# HM_Nightfall-mini-2e_v1.net
KiCad netlist of a schematic drawn in EAGLE
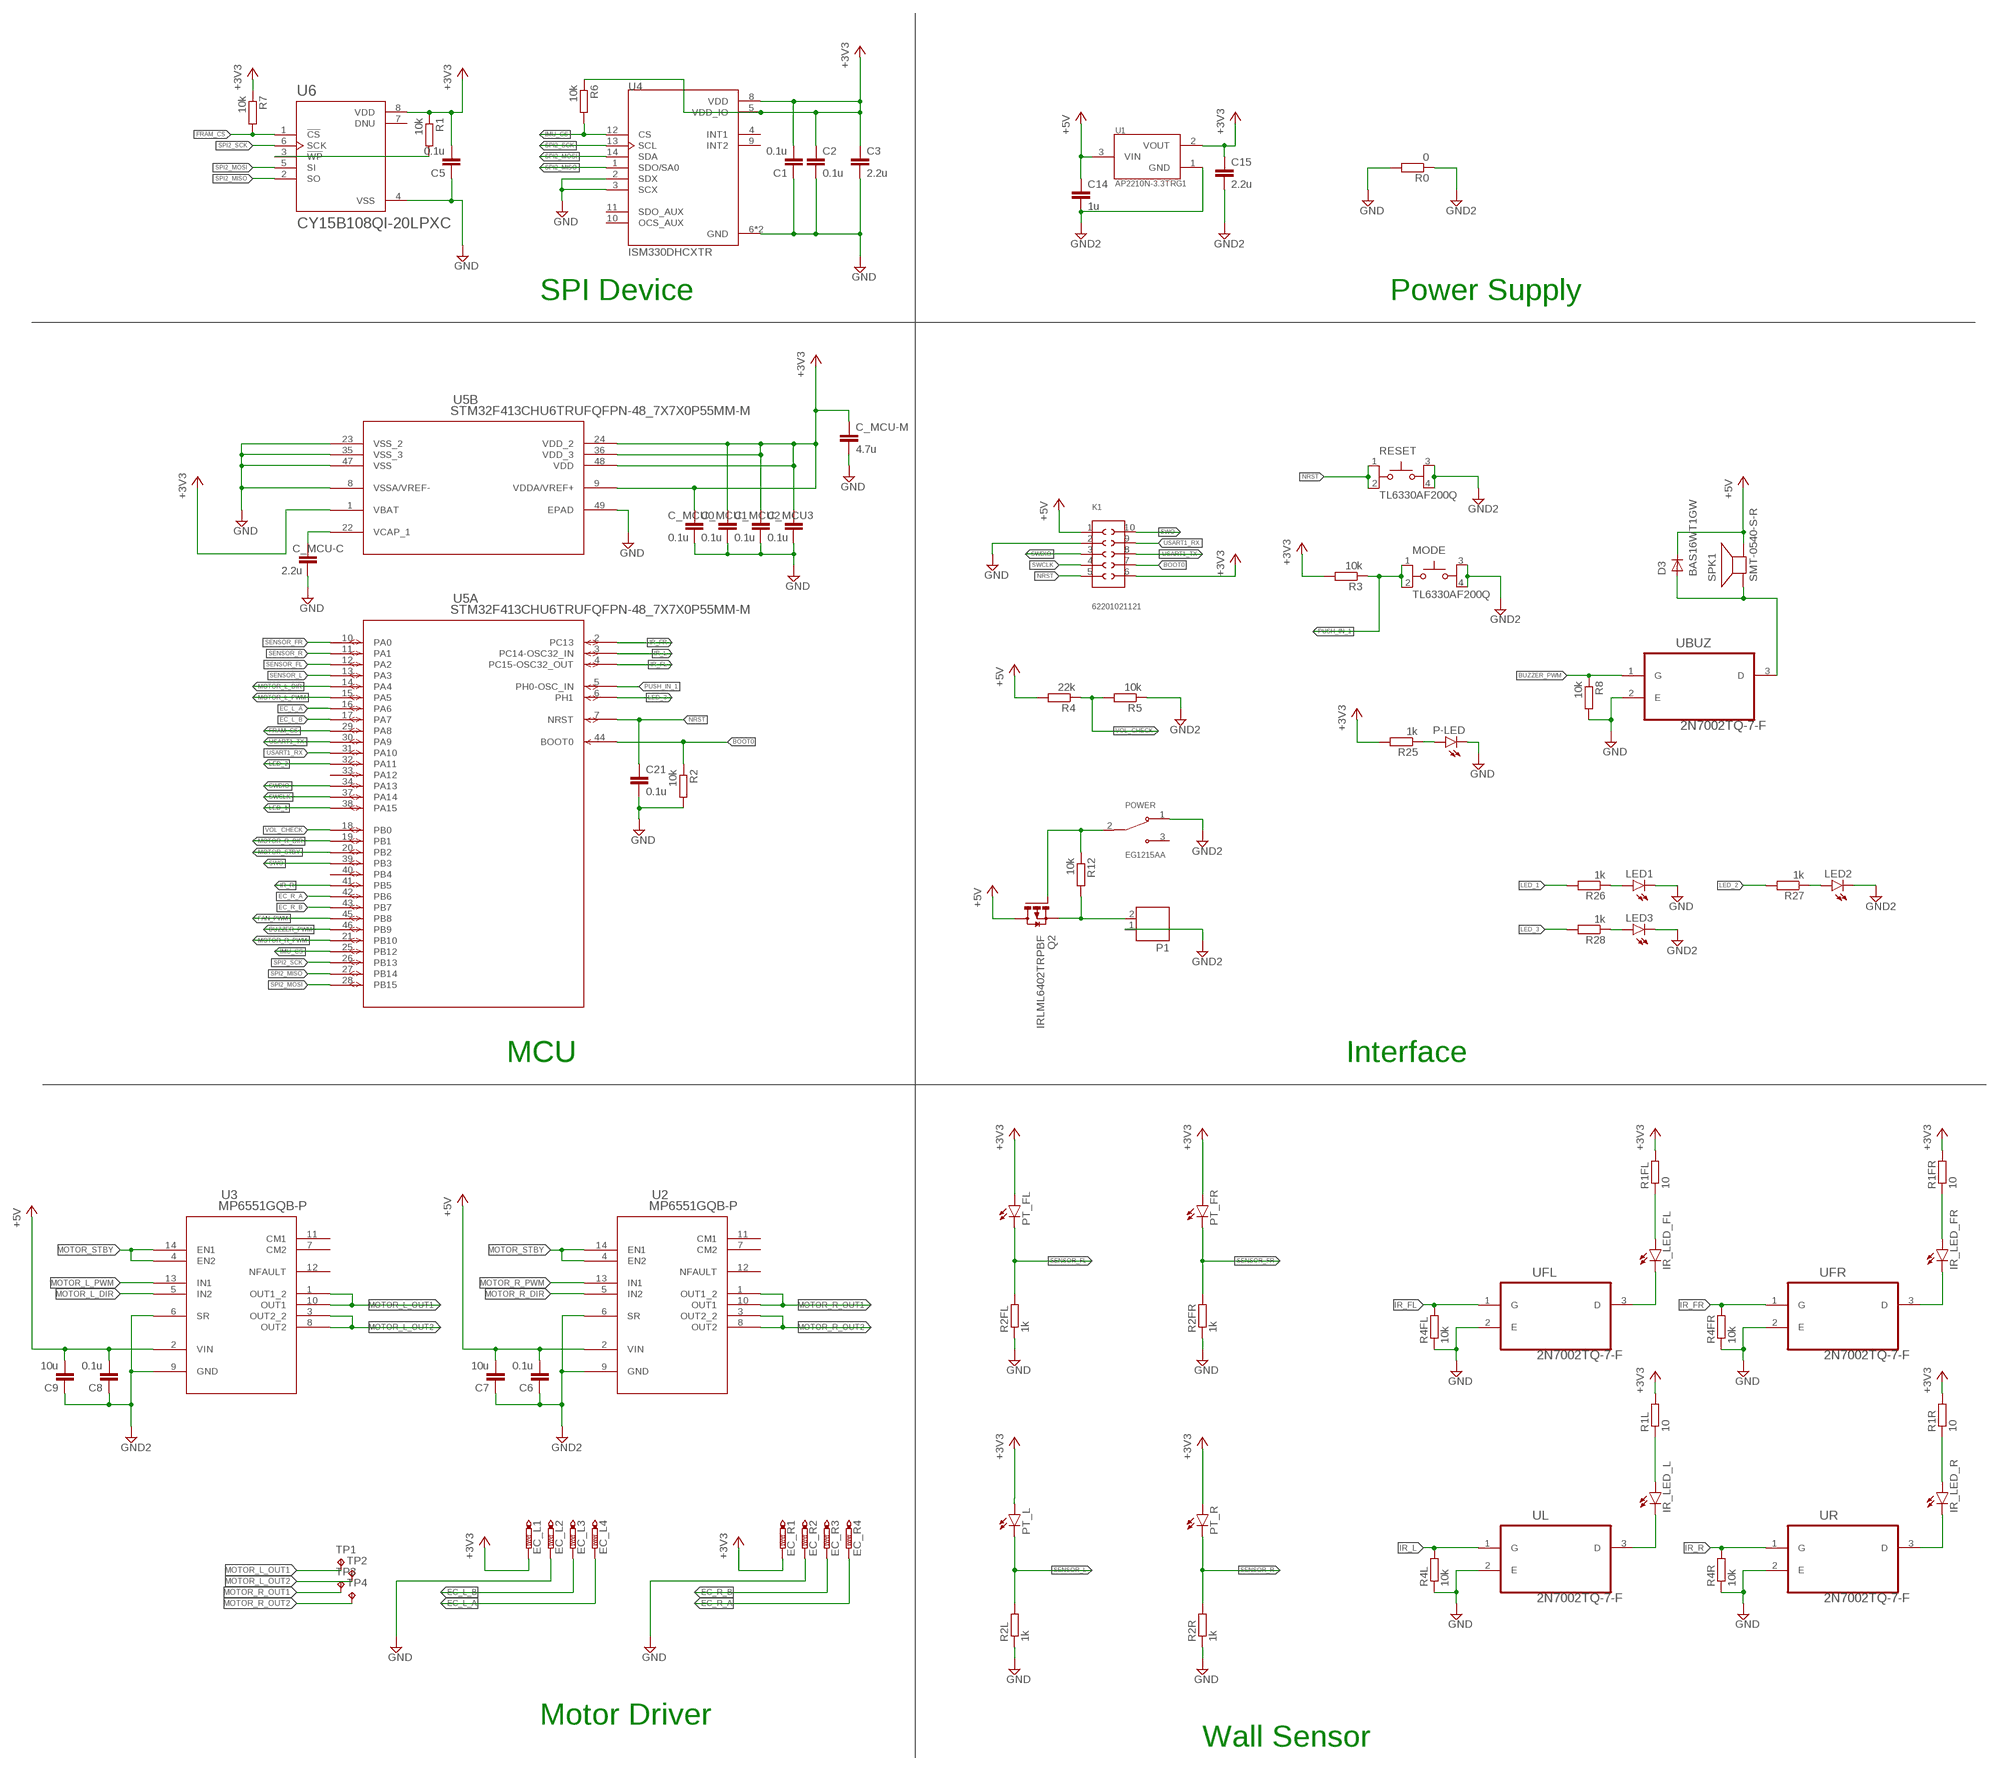
[diagram p0: schematic, sheet 1]

(export (version "E")
  (design (tool "Eeschema 10.0.6"))
  (components
    (comp (ref "C1")
      (value "0.1u")
      (footprint "eagle-import:C0402")
      (libsource (lib "eagle-import") (part "C-EUC0402"))
    )
    (comp (ref "C2")
      (value "0.1u")
      (footprint "eagle-import:C0402")
      (libsource (lib "eagle-import") (part "C-EUC0402"))
    )
    (comp (ref "C3")
      (value "2.2u")
      (footprint "eagle-import:C0402")
      (libsource (lib "eagle-import") (part "C-EUC0402"))
    )
    (comp (ref "C5")
      (value "0.1u")
      (footprint "eagle-import:C0402")
      (libsource (lib "eagle-import") (part "C-EUC0402"))
    )
    (comp (ref "C6")
      (value "0.1u")
      (footprint "eagle-import:C0402")
      (libsource (lib "eagle-import") (part "C-EUC0402"))
    )
    (comp (ref "C7")
      (value "10u")
      (footprint "eagle-import:C0402")
      (libsource (lib "eagle-import") (part "C-EUC0402"))
    )
    (comp (ref "C8")
      (value "0.1u")
      (footprint "eagle-import:C0402")
      (libsource (lib "eagle-import") (part "C-EUC0402"))
    )
    (comp (ref "C9")
      (value "10u")
      (footprint "eagle-import:C0402")
      (libsource (lib "eagle-import") (part "C-EUC0402"))
    )
    (comp (ref "C14")
      (value "1u")
      (footprint "eagle-import:C0402")
      (libsource (lib "eagle-import") (part "C-EUC0402"))
    )
    (comp (ref "C15")
      (value "2.2u")
      (footprint "eagle-import:C0402")
      (libsource (lib "eagle-import") (part "C-EUC0402"))
    )
    (comp (ref "C21")
      (value "0.1u")
      (footprint "eagle-import:C0402")
      (libsource (lib "eagle-import") (part "C-EUC0402"))
    )
    (comp (ref "C_MCU-C")
      (value "2.2u")
      (footprint "eagle-import:C0402")
      (libsource (lib "eagle-import") (part "C-EUC0402"))
    )
    (comp (ref "C_MCU-M")
      (value "4.7u")
      (footprint "eagle-import:C0402")
      (libsource (lib "eagle-import") (part "C-EUC0402"))
    )
    (comp (ref "C_MCU0")
      (value "0.1u")
      (footprint "eagle-import:C0402")
      (libsource (lib "eagle-import") (part "C-EUC0402"))
    )
    (comp (ref "C_MCU1")
      (value "0.1u")
      (footprint "eagle-import:C0402")
      (libsource (lib "eagle-import") (part "C-EUC0402"))
    )
    (comp (ref "C_MCU2")
      (value "0.1u")
      (footprint "eagle-import:C0402")
      (libsource (lib "eagle-import") (part "C-EUC0402"))
    )
    (comp (ref "C_MCU3")
      (value "0.1u")
      (footprint "eagle-import:C0402")
      (libsource (lib "eagle-import") (part "C-EUC0402"))
    )
    (comp (ref "D3")
      (value "BAS16WT1GW")
      (footprint "eagle-import:SOT323")
      (fields (field (name "MF") "ON Semiconductor") (field (name "MP") "BAS16WT1G"))
      (libsource (lib "eagle-import") (part "BAS16WT1GW"))
    )
    (comp (ref "EC_L1")
      (value "PTR1TP06SQ")
      (footprint "eagle-import:TP06SQ")
      (libsource (lib "eagle-import") (part "PTR1TP06SQ"))
    )
    (comp (ref "EC_L2")
      (value "PTR1TP06SQ")
      (footprint "eagle-import:TP06SQ")
      (libsource (lib "eagle-import") (part "PTR1TP06SQ"))
    )
    (comp (ref "EC_L3")
      (value "PTR1TP06SQ")
      (footprint "eagle-import:TP06SQ")
      (libsource (lib "eagle-import") (part "PTR1TP06SQ"))
    )
    (comp (ref "EC_L4")
      (value "PTR1TP06SQ")
      (footprint "eagle-import:TP06SQ")
      (libsource (lib "eagle-import") (part "PTR1TP06SQ"))
    )
    (comp (ref "EC_R1")
      (value "PTR1TP06SQ")
      (footprint "eagle-import:TP06SQ")
      (libsource (lib "eagle-import") (part "PTR1TP06SQ"))
    )
    (comp (ref "EC_R2")
      (value "PTR1TP06SQ")
      (footprint "eagle-import:TP06SQ")
      (libsource (lib "eagle-import") (part "PTR1TP06SQ"))
    )
    (comp (ref "EC_R3")
      (value "PTR1TP06SQ")
      (footprint "eagle-import:TP06SQ")
      (libsource (lib "eagle-import") (part "PTR1TP06SQ"))
    )
    (comp (ref "EC_R4")
      (value "PTR1TP06SQ")
      (footprint "eagle-import:TP06SQ")
      (libsource (lib "eagle-import") (part "PTR1TP06SQ"))
    )
    (comp (ref "IR_LED_FL")
      (value "LED3MM")
      (footprint "eagle-import:LED3MM")
      (libsource (lib "eagle-import") (part "LED3MM"))
    )
    (comp (ref "IR_LED_FR")
      (value "LED3MM")
      (footprint "eagle-import:LED3MM")
      (libsource (lib "eagle-import") (part "LED3MM"))
    )
    (comp (ref "IR_LED_L")
      (value "LED3MM")
      (footprint "eagle-import:LED3MM")
      (libsource (lib "eagle-import") (part "LED3MM"))
    )
    (comp (ref "IR_LED_R")
      (value "LED3MM")
      (footprint "eagle-import:LED3MM")
      (libsource (lib "eagle-import") (part "LED3MM"))
    )
    (comp (ref "K1")
      (value "62201021121")
      (footprint "eagle-import:62201021121")
      (libsource (lib "eagle-import") (part "62201021121"))
    )
    (comp (ref "LED1")
      (value "LEDCHIPLED_0603")
      (footprint "eagle-import:CHIPLED_0603")
      (libsource (lib "eagle-import") (part "LEDCHIPLED_0603"))
    )
    (comp (ref "LED2")
      (value "LEDCHIPLED_0603")
      (footprint "eagle-import:CHIPLED_0603")
      (libsource (lib "eagle-import") (part "LEDCHIPLED_0603"))
    )
    (comp (ref "LED3")
      (value "LEDCHIPLED_0603")
      (footprint "eagle-import:CHIPLED_0603")
      (libsource (lib "eagle-import") (part "LEDCHIPLED_0603"))
    )
    (comp (ref "MODE")
      (value "TL6330AF200Q")
      (footprint "eagle-import:SW_TL6330AF200Q")
      (fields (field (name "MF") "E-Switch"))
      (libsource (lib "eagle-import") (part "TL6330AF200Q"))
    )
    (comp (ref "P-LED")
      (value "LEDCHIPLED_0603")
      (footprint "eagle-import:CHIPLED_0603")
      (libsource (lib "eagle-import") (part "LEDCHIPLED_0603"))
    )
    (comp (ref "P1")
      (value "JST-PH2")
      (footprint "eagle-import:JST-PH2")
      (libsource (lib "eagle-import") (part "JST-PH2"))
    )
    (comp (ref "POWER")
      (value "EG1215AA")
      (footprint "eagle-import:SW_EG1215AA")
      (fields (field (name "MF") "E-Switch"))
      (libsource (lib "eagle-import") (part "EG1215AA"))
    )
    (comp (ref "PT_FL")
      (value "LED3MM")
      (footprint "eagle-import:LED3MM")
      (libsource (lib "eagle-import") (part "LED3MM"))
    )
    (comp (ref "PT_FR")
      (value "LED3MM")
      (footprint "eagle-import:LED3MM")
      (libsource (lib "eagle-import") (part "LED3MM"))
    )
    (comp (ref "PT_L")
      (value "LED3MM")
      (footprint "eagle-import:LED3MM")
      (libsource (lib "eagle-import") (part "LED3MM"))
    )
    (comp (ref "PT_R")
      (value "LED3MM")
      (footprint "eagle-import:LED3MM")
      (libsource (lib "eagle-import") (part "LED3MM"))
    )
    (comp (ref "Q2")
      (value "IRLML6402TRPBF")
      (footprint "eagle-import:SOT23")
      (fields (field (name "MF") "Infineon Technologies") (field (name "MP") "IRLML6402"))
      (libsource (lib "eagle-import") (part "IRLML6402TRPBF"))
    )
    (comp (ref "R0")
      (value "0")
      (footprint "eagle-import:R0402")
      (libsource (lib "eagle-import") (part "R-EU_R0402"))
    )
    (comp (ref "R1")
      (value "10k")
      (footprint "eagle-import:R0402")
      (libsource (lib "eagle-import") (part "R-EU_R0402"))
    )
    (comp (ref "R1FL")
      (value "10")
      (footprint "eagle-import:R0402")
      (libsource (lib "eagle-import") (part "R-EU_R0402"))
    )
    (comp (ref "R1FR")
      (value "10")
      (footprint "eagle-import:R0402")
      (libsource (lib "eagle-import") (part "R-EU_R0402"))
    )
    (comp (ref "R1L")
      (value "10")
      (footprint "eagle-import:R0402")
      (libsource (lib "eagle-import") (part "R-EU_R0402"))
    )
    (comp (ref "R1R")
      (value "10")
      (footprint "eagle-import:R0402")
      (libsource (lib "eagle-import") (part "R-EU_R0402"))
    )
    (comp (ref "R2")
      (value "10k")
      (footprint "eagle-import:R0402")
      (libsource (lib "eagle-import") (part "R-EU_R0402"))
    )
    (comp (ref "R2FL")
      (value "1k")
      (footprint "eagle-import:R0402")
      (libsource (lib "eagle-import") (part "R-EU_R0402"))
    )
    (comp (ref "R2FR")
      (value "1k")
      (footprint "eagle-import:R0402")
      (libsource (lib "eagle-import") (part "R-EU_R0402"))
    )
    (comp (ref "R2L")
      (value "1k")
      (footprint "eagle-import:R0402")
      (libsource (lib "eagle-import") (part "R-EU_R0402"))
    )
    (comp (ref "R2R")
      (value "1k")
      (footprint "eagle-import:R0402")
      (libsource (lib "eagle-import") (part "R-EU_R0402"))
    )
    (comp (ref "R3")
      (value "10k")
      (footprint "eagle-import:R0402")
      (libsource (lib "eagle-import") (part "R-EU_R0402"))
    )
    (comp (ref "R4")
      (value "22k")
      (footprint "eagle-import:R0402")
      (libsource (lib "eagle-import") (part "R-EU_R0402"))
    )
    (comp (ref "R4FL")
      (value "10k")
      (footprint "eagle-import:R0402")
      (libsource (lib "eagle-import") (part "R-EU_R0402"))
    )
    (comp (ref "R4FR")
      (value "10k")
      (footprint "eagle-import:R0402")
      (libsource (lib "eagle-import") (part "R-EU_R0402"))
    )
    (comp (ref "R4L")
      (value "10k")
      (footprint "eagle-import:R0402")
      (libsource (lib "eagle-import") (part "R-EU_R0402"))
    )
    (comp (ref "R4R")
      (value "10k")
      (footprint "eagle-import:R0402")
      (libsource (lib "eagle-import") (part "R-EU_R0402"))
    )
    (comp (ref "R5")
      (value "10k")
      (footprint "eagle-import:R0402")
      (libsource (lib "eagle-import") (part "R-EU_R0402"))
    )
    (comp (ref "R6")
      (value "10k")
      (footprint "eagle-import:R0402")
      (libsource (lib "eagle-import") (part "R-EU_R0402"))
    )
    (comp (ref "R7")
      (value "10k")
      (footprint "eagle-import:R0402")
      (libsource (lib "eagle-import") (part "R-EU_R0402"))
    )
    (comp (ref "R8")
      (value "10k")
      (footprint "eagle-import:R0402")
      (libsource (lib "eagle-import") (part "R-EU_R0402"))
    )
    (comp (ref "R12")
      (value "10k")
      (footprint "eagle-import:R0402")
      (libsource (lib "eagle-import") (part "R-EU_R0402"))
    )
    (comp (ref "R25")
      (value "1k")
      (footprint "eagle-import:R0402")
      (libsource (lib "eagle-import") (part "R-EU_R0402"))
    )
    (comp (ref "R26")
      (value "1k")
      (footprint "eagle-import:R0402")
      (libsource (lib "eagle-import") (part "R-EU_R0402"))
    )
    (comp (ref "R27")
      (value "1k")
      (footprint "eagle-import:R0402")
      (libsource (lib "eagle-import") (part "R-EU_R0402"))
    )
    (comp (ref "R28")
      (value "1k")
      (footprint "eagle-import:R0402")
      (libsource (lib "eagle-import") (part "R-EU_R0402"))
    )
    (comp (ref "RESET")
      (value "TL6330AF200Q")
      (footprint "eagle-import:SW_TL6330AF200Q")
      (fields (field (name "MF") "E-Switch"))
      (libsource (lib "eagle-import") (part "TL6330AF200Q"))
    )
    (comp (ref "SPK1")
      (value "SMT-0540-S-R")
      (footprint "eagle-import:SMT-0540-S-R")
      (fields (field (name "DIGI-KEY_PART_NUMBER") "668-1060-1-ND") (field (name "MF") "PUI"))
      (libsource (lib "eagle-import") (part "SMT-0540-S-R"))
    )
    (comp (ref "TP1")
      (value "TPB1,27")
      (footprint "eagle-import:B1,27")
      (libsource (lib "eagle-import") (part "TPB1,27"))
    )
    (comp (ref "TP2")
      (value "TPB1,27")
      (footprint "eagle-import:B1,27")
      (libsource (lib "eagle-import") (part "TPB1,27"))
    )
    (comp (ref "TP3")
      (value "TPB1,27")
      (footprint "eagle-import:B1,27")
      (libsource (lib "eagle-import") (part "TPB1,27"))
    )
    (comp (ref "TP4")
      (value "TPB1,27")
      (footprint "eagle-import:B1,27")
      (libsource (lib "eagle-import") (part "TPB1,27"))
    )
    (comp (ref "U1")
      (value "AP2210N-3.3TRG1")
      (footprint "eagle-import:SOT95P280X145-3N")
      (fields (field (name "MF") "Diodes Inc."))
      (libsource (lib "eagle-import") (part "AP2210N-3.3TRG1"))
    )
    (comp (ref "U2")
      (value "MP6551GQB-P")
      (footprint "eagle-import:QFN-14_MP6551_MNP")
      (fields (field (name "COPYRIGHT") "Copyright (C) 2025 Ultra Librarian. All rights reserved."))
      (libsource (lib "eagle-import") (part "MP6551GQB-P"))
    )
    (comp (ref "U3")
      (value "MP6551GQB-P")
      (footprint "eagle-import:QFN-14_MP6551_MNP")
      (fields (field (name "COPYRIGHT") "Copyright (C) 2025 Ultra Librarian. All rights reserved."))
      (libsource (lib "eagle-import") (part "MP6551GQB-P"))
    )
    (comp (ref "U4")
      (value "ISM330DHCXTR")
      (footprint "eagle-import:PQFN50P250X300X86-14N")
      (fields (field (name "MF") "STMicroelectronics"))
      (libsource (lib "eagle-import") (part "ISM330DHCXTR"))
    )
    (comp (ref "U5")
      (value "STM32F413CHU6TRUFQFPN-48_7X7X0P55MM-M")
      (footprint "eagle-import:UFQFPN-48_7X7X0P55MM-M")
      (fields
        (field (name "MANUFACTURER_PART_NUMBER") "STM32F413CHU6TR")
        (field (name "COPYRIGHT") "Copyright (C) 2026 Ultra Librarian. All rights reserved.")
      )
      (libsource (lib "eagle-import") (part "STM32F413CHU6TRUFQFPN-48_7X7X0P55MM-M"))
    )
    (comp (ref "U6")
      (value "CY15B108QI-20LPXC")
      (footprint "eagle-import:SON65P328X323X55-8N")
      (fields (field (name "MF") "Cypress Semiconductor"))
      (libsource (lib "eagle-import") (part "CY15B108QI-20LPXC"))
    )
    (comp (ref "UBUZ")
      (value "2N7002TQ-7-F")
      (footprint "eagle-import:SOT50P160X90-3N")
      (fields (field (name "MF") "Diodes Inc."))
      (libsource (lib "eagle-import") (part "2N7002TQ-7-F"))
    )
    (comp (ref "UFL")
      (value "2N7002TQ-7-F")
      (footprint "eagle-import:SOT50P160X90-3N")
      (fields (field (name "MF") "Diodes Inc."))
      (libsource (lib "eagle-import") (part "2N7002TQ-7-F"))
    )
    (comp (ref "UFR")
      (value "2N7002TQ-7-F")
      (footprint "eagle-import:SOT50P160X90-3N")
      (fields (field (name "MF") "Diodes Inc."))
      (libsource (lib "eagle-import") (part "2N7002TQ-7-F"))
    )
    (comp (ref "UL")
      (value "2N7002TQ-7-F")
      (footprint "eagle-import:SOT50P160X90-3N")
      (fields (field (name "MF") "Diodes Inc."))
      (libsource (lib "eagle-import") (part "2N7002TQ-7-F"))
    )
    (comp (ref "UR")
      (value "2N7002TQ-7-F")
      (footprint "eagle-import:SOT50P160X90-3N")
      (fields (field (name "MF") "Diodes Inc."))
      (libsource (lib "eagle-import") (part "2N7002TQ-7-F"))
    )
  )
  (nets
    (net (code "1") (name "+3V3") (class "Default")
      (node (ref "C1") (pin "2") (pinfunction "2_2") (pintype "passive"))
      (node (ref "C15") (pin "1") (pinfunction "1_1") (pintype "passive"))
      (node (ref "C2") (pin "1") (pinfunction "1_1") (pintype "passive"))
      (node (ref "C3") (pin "1") (pinfunction "1_1") (pintype "passive"))
      (node (ref "C5") (pin "2") (pinfunction "2_2") (pintype "passive"))
      (node (ref "C_MCU-M") (pin "1") (pinfunction "1_1") (pintype "passive"))
      (node (ref "C_MCU0") (pin "1") (pinfunction "1_1") (pintype "passive"))
      (node (ref "C_MCU1") (pin "1") (pinfunction "1_1") (pintype "passive"))
      (node (ref "C_MCU2") (pin "1") (pinfunction "1_1") (pintype "passive"))
      (node (ref "C_MCU3") (pin "1") (pinfunction "1_1") (pintype "passive"))
      (node (ref "EC_L1") (pin "TP") (pinfunction "TP_TP") (pintype "input"))
      (node (ref "EC_R1") (pin "TP") (pinfunction "TP_TP") (pintype "input"))
      (node (ref "K1") (pin "6") (pinfunction "6_6") (pintype "passive"))
      (node (ref "PT_FL") (pin "A") (pinfunction "A_A") (pintype "passive"))
      (node (ref "PT_FR") (pin "A") (pinfunction "A_A") (pintype "passive"))
      (node (ref "PT_L") (pin "A") (pinfunction "A_A") (pintype "passive"))
      (node (ref "PT_R") (pin "A") (pinfunction "A_A") (pintype "passive"))
      (node (ref "R1") (pin "1") (pinfunction "1_1") (pintype "passive"))
      (node (ref "R1FL") (pin "2") (pinfunction "2_2") (pintype "passive"))
      (node (ref "R1FR") (pin "2") (pinfunction "2_2") (pintype "passive"))
      (node (ref "R1L") (pin "2") (pinfunction "2_2") (pintype "passive"))
      (node (ref "R1R") (pin "2") (pinfunction "2_2") (pintype "passive"))
      (node (ref "R25") (pin "2") (pinfunction "2_2") (pintype "passive"))
      (node (ref "R3") (pin "2") (pinfunction "2_2") (pintype "passive"))
      (node (ref "R6") (pin "1") (pinfunction "1_1") (pintype "passive"))
      (node (ref "R7") (pin "1") (pinfunction "1_1") (pintype "passive"))
      (node (ref "U1") (pin "2") (pinfunction "VOUT_2") (pintype "output"))
      (node (ref "U4") (pin "5") (pinfunction "VDD_IO_5") (pintype "power_in"))
      (node (ref "U4") (pin "8") (pinfunction "VDD_8") (pintype "power_in"))
      (node (ref "U5") (pin "1") (pinfunction "VBAT_1") (pintype "power_in"))
      (node (ref "U5") (pin "24") (pinfunction "VDD_2_24") (pintype "power_in"))
      (node (ref "U5") (pin "36") (pinfunction "VDD_3_36") (pintype "power_in"))
      (node (ref "U5") (pin "48") (pinfunction "VDD_48") (pintype "power_in"))
      (node (ref "U5") (pin "9") (pinfunction "VDDA/VREF+_9") (pintype "power_in"))
      (node (ref "U6") (pin "8") (pinfunction "VDD_8") (pintype "power_in"))
    )
    (net (code "2") (name "+5V") (class "Default")
      (node (ref "C14") (pin "1") (pinfunction "1_1") (pintype "passive"))
      (node (ref "C6") (pin "2") (pinfunction "2_2") (pintype "passive"))
      (node (ref "C7") (pin "2") (pinfunction "2_2") (pintype "passive"))
      (node (ref "C8") (pin "2") (pinfunction "2_2") (pintype "passive"))
      (node (ref "C9") (pin "2") (pinfunction "2_2") (pintype "passive"))
      (node (ref "D3") (pin "3") (pinfunction "K_3") (pintype "passive"))
      (node (ref "K1") (pin "1") (pinfunction "1_1") (pintype "passive"))
      (node (ref "Q2") (pin "3") (pinfunction "D_3") (pintype "passive"))
      (node (ref "R4") (pin "2") (pinfunction "2_2") (pintype "passive"))
      (node (ref "SPK1") (pin "+") (pinfunction "-_+") (pintype "passive"))
      (node (ref "U1") (pin "3") (pinfunction "VIN_3") (pintype "input"))
      (node (ref "U2") (pin "2") (pinfunction "VIN_2") (pintype "power_in"))
      (node (ref "U3") (pin "2") (pinfunction "VIN_2") (pintype "power_in"))
    )
    (net (code "3") (name "BOOT0") (class "Default")
      (node (ref "K1") (pin "7") (pinfunction "7_7") (pintype "passive"))
      (node (ref "R2") (pin "1") (pinfunction "1_1") (pintype "passive"))
      (node (ref "U5") (pin "44") (pinfunction "BOOT0_44") (pintype "input"))
    )
    (net (code "4") (name "BUZZER_PWM") (class "Default")
      (node (ref "R8") (pin "1") (pinfunction "1_1") (pintype "passive"))
      (node (ref "U5") (pin "46") (pinfunction "PB9_46") (pintype "bidirectional"))
      (node (ref "UBUZ") (pin "1") (pinfunction "G_1") (pintype "passive"))
    )
    (net (code "5") (name "EC_L_A") (class "Default")
      (node (ref "EC_L4") (pin "TP") (pinfunction "TP_TP") (pintype "input"))
      (node (ref "U5") (pin "16") (pinfunction "PA6_16") (pintype "bidirectional"))
    )
    (net (code "6") (name "EC_L_B") (class "Default")
      (node (ref "EC_L3") (pin "TP") (pinfunction "TP_TP") (pintype "input"))
      (node (ref "U5") (pin "17") (pinfunction "PA7_17") (pintype "bidirectional"))
    )
    (net (code "7") (name "EC_R_A") (class "Default")
      (node (ref "EC_R4") (pin "TP") (pinfunction "TP_TP") (pintype "input"))
      (node (ref "U5") (pin "42") (pinfunction "PB6_42") (pintype "bidirectional"))
    )
    (net (code "8") (name "EC_R_B") (class "Default")
      (node (ref "EC_R3") (pin "TP") (pinfunction "TP_TP") (pintype "input"))
      (node (ref "U5") (pin "43") (pinfunction "PB7_43") (pintype "bidirectional"))
    )
    (net (code "9") (name "FAN_PWM") (class "Default")
      (node (ref "U5") (pin "45") (pinfunction "PB8_45") (pintype "bidirectional"))
    )
    (net (code "10") (name "FRAM_CS") (class "Default")
      (node (ref "R7") (pin "2") (pinfunction "2_2") (pintype "passive"))
      (node (ref "U5") (pin "29") (pinfunction "PA8_29") (pintype "bidirectional"))
      (node (ref "U6") (pin "1") (pinfunction "~{CS}_1") (pintype "input"))
    )
    (net (code "11") (name "GND") (class "Default")
      (node (ref "C1") (pin "1") (pinfunction "1_1") (pintype "passive"))
      (node (ref "C2") (pin "2") (pinfunction "2_2") (pintype "passive"))
      (node (ref "C21") (pin "2") (pinfunction "2_2") (pintype "passive"))
      (node (ref "C3") (pin "2") (pinfunction "2_2") (pintype "passive"))
      (node (ref "C5") (pin "1") (pinfunction "1_1") (pintype "passive"))
      (node (ref "C_MCU-C") (pin "2") (pinfunction "2_2") (pintype "passive"))
      (node (ref "C_MCU-M") (pin "2") (pinfunction "2_2") (pintype "passive"))
      (node (ref "C_MCU0") (pin "2") (pinfunction "2_2") (pintype "passive"))
      (node (ref "C_MCU1") (pin "2") (pinfunction "2_2") (pintype "passive"))
      (node (ref "C_MCU2") (pin "2") (pinfunction "2_2") (pintype "passive"))
      (node (ref "C_MCU3") (pin "2") (pinfunction "2_2") (pintype "passive"))
      (node (ref "EC_L2") (pin "TP") (pinfunction "TP_TP") (pintype "input"))
      (node (ref "EC_R2") (pin "TP") (pinfunction "TP_TP") (pintype "input"))
      (node (ref "K1") (pin "2") (pinfunction "2_2") (pintype "passive"))
      (node (ref "LED1") (pin "C") (pinfunction "C_C") (pintype "passive"))
      (node (ref "P-LED") (pin "C") (pinfunction "C_C") (pintype "passive"))
      (node (ref "R0") (pin "2") (pinfunction "2_2") (pintype "passive"))
      (node (ref "R2") (pin "2") (pinfunction "2_2") (pintype "passive"))
      (node (ref "R2FL") (pin "1") (pinfunction "1_1") (pintype "passive"))
      (node (ref "R2FR") (pin "1") (pinfunction "1_1") (pintype "passive"))
      (node (ref "R2L") (pin "1") (pinfunction "1_1") (pintype "passive"))
      (node (ref "R2R") (pin "1") (pinfunction "1_1") (pintype "passive"))
      (node (ref "R4FL") (pin "1") (pinfunction "1_1") (pintype "passive"))
      (node (ref "R4FR") (pin "1") (pinfunction "1_1") (pintype "passive"))
      (node (ref "R4L") (pin "1") (pinfunction "1_1") (pintype "passive"))
      (node (ref "R4R") (pin "1") (pinfunction "1_1") (pintype "passive"))
      (node (ref "R8") (pin "2") (pinfunction "2_2") (pintype "passive"))
      (node (ref "U4") (pin "2") (pinfunction "SDX_2") (pintype "bidirectional"))
      (node (ref "U4") (pin "3") (pinfunction "SCX_3") (pintype "bidirectional"))
      (node (ref "U4") (pin "6") (pinfunction "GND_6") (pintype "power_in"))
      (node (ref "U4") (pin "7") (pinfunction "GND_7") (pintype "power_in"))
      (node (ref "U5") (pin "23") (pinfunction "VSS_2_23") (pintype "power_in"))
      (node (ref "U5") (pin "35") (pinfunction "VSS_3_35") (pintype "power_in"))
      (node (ref "U5") (pin "47") (pinfunction "VSS_47") (pintype "power_in"))
      (node (ref "U5") (pin "49") (pinfunction "EPAD_49") (pintype "passive"))
      (node (ref "U5") (pin "8") (pinfunction "VSSA/VREF-_8") (pintype "power_in"))
      (node (ref "U6") (pin "4") (pinfunction "VSS_4") (pintype "power_in"))
      (node (ref "UBUZ") (pin "2") (pinfunction "E_2") (pintype "passive"))
      (node (ref "UFL") (pin "2") (pinfunction "E_2") (pintype "passive"))
      (node (ref "UFR") (pin "2") (pinfunction "E_2") (pintype "passive"))
      (node (ref "UL") (pin "2") (pinfunction "E_2") (pintype "passive"))
      (node (ref "UR") (pin "2") (pinfunction "E_2") (pintype "passive"))
    )
    (net (code "12") (name "GND2") (class "Default")
      (node (ref "C14") (pin "2") (pinfunction "2_2") (pintype "passive"))
      (node (ref "C15") (pin "2") (pinfunction "2_2") (pintype "passive"))
      (node (ref "C6") (pin "1") (pinfunction "1_1") (pintype "passive"))
      (node (ref "C7") (pin "1") (pinfunction "1_1") (pintype "passive"))
      (node (ref "C8") (pin "1") (pinfunction "1_1") (pintype "passive"))
      (node (ref "C9") (pin "1") (pinfunction "1_1") (pintype "passive"))
      (node (ref "LED2") (pin "C") (pinfunction "C_C") (pintype "passive"))
      (node (ref "LED3") (pin "C") (pinfunction "C_C") (pintype "passive"))
      (node (ref "MODE") (pin "3") (pinfunction "3_3") (pintype "passive"))
      (node (ref "MODE") (pin "4") (pinfunction "4_4") (pintype "passive"))
      (node (ref "P1") (pin "1") (pinfunction "1_1") (pintype "passive"))
      (node (ref "POWER") (pin "1") (pinfunction "1_1") (pintype "passive"))
      (node (ref "R0") (pin "1") (pinfunction "1_1") (pintype "passive"))
      (node (ref "R5") (pin "1") (pinfunction "1_1") (pintype "passive"))
      (node (ref "RESET") (pin "3") (pinfunction "3_3") (pintype "passive"))
      (node (ref "RESET") (pin "4") (pinfunction "4_4") (pintype "passive"))
      (node (ref "U1") (pin "1") (pinfunction "GND_1") (pintype "power_in"))
      (node (ref "U2") (pin "6") (pinfunction "SR_6") (pintype "passive"))
      (node (ref "U2") (pin "9") (pinfunction "GND_9") (pintype "power_in"))
      (node (ref "U3") (pin "6") (pinfunction "SR_6") (pintype "passive"))
      (node (ref "U3") (pin "9") (pinfunction "GND_9") (pintype "power_in"))
    )
    (net (code "13") (name "IMU_CS") (class "Default")
      (node (ref "R6") (pin "2") (pinfunction "2_2") (pintype "passive"))
      (node (ref "U4") (pin "12") (pinfunction "CS_12") (pintype "input"))
      (node (ref "U5") (pin "25") (pinfunction "PB12_25") (pintype "bidirectional"))
    )
    (net (code "14") (name "IR_FL") (class "Default")
      (node (ref "R4FL") (pin "2") (pinfunction "2_2") (pintype "passive"))
      (node (ref "U5") (pin "4") (pinfunction "PC15-OSC32_OUT_4") (pintype "bidirectional"))
      (node (ref "UFL") (pin "1") (pinfunction "G_1") (pintype "passive"))
    )
    (net (code "15") (name "IR_FR") (class "Default")
      (node (ref "R4FR") (pin "2") (pinfunction "2_2") (pintype "passive"))
      (node (ref "U5") (pin "2") (pinfunction "PC13_2") (pintype "bidirectional"))
      (node (ref "UFR") (pin "1") (pinfunction "G_1") (pintype "passive"))
    )
    (net (code "16") (name "IR_L") (class "Default")
      (node (ref "R4L") (pin "2") (pinfunction "2_2") (pintype "passive"))
      (node (ref "U5") (pin "3") (pinfunction "PC14-OSC32_IN_3") (pintype "bidirectional"))
      (node (ref "UL") (pin "1") (pinfunction "G_1") (pintype "passive"))
    )
    (net (code "17") (name "IR_R") (class "Default")
      (node (ref "R4R") (pin "2") (pinfunction "2_2") (pintype "passive"))
      (node (ref "U5") (pin "41") (pinfunction "PB5_41") (pintype "bidirectional"))
      (node (ref "UR") (pin "1") (pinfunction "G_1") (pintype "passive"))
    )
    (net (code "18") (name "LED_1") (class "Default")
      (node (ref "R26") (pin "2") (pinfunction "2_2") (pintype "passive"))
      (node (ref "U5") (pin "38") (pinfunction "PA15_38") (pintype "bidirectional"))
    )
    (net (code "19") (name "LED_2") (class "Default")
      (node (ref "R27") (pin "2") (pinfunction "2_2") (pintype "passive"))
      (node (ref "U5") (pin "32") (pinfunction "PA11_32") (pintype "bidirectional"))
    )
    (net (code "20") (name "LED_3") (class "Default")
      (node (ref "R28") (pin "2") (pinfunction "2_2") (pintype "passive"))
      (node (ref "U5") (pin "6") (pinfunction "PH1_6") (pintype "bidirectional"))
    )
    (net (code "21") (name "MOTOR_L_DIR") (class "Default")
      (node (ref "U3") (pin "5") (pinfunction "IN2_5") (pintype "input"))
      (node (ref "U5") (pin "14") (pinfunction "PA4_14") (pintype "bidirectional"))
    )
    (net (code "22") (name "MOTOR_L_OUT1") (class "Default")
      (node (ref "TP1") (pin "TP") (pinfunction "TP_TP") (pintype "input"))
      (node (ref "U3") (pin "1") (pinfunction "OUT1_2_1") (pintype "output"))
      (node (ref "U3") (pin "10") (pinfunction "OUT1_10") (pintype "output"))
    )
    (net (code "23") (name "MOTOR_L_OUT2") (class "Default")
      (node (ref "TP2") (pin "TP") (pinfunction "TP_TP") (pintype "input"))
      (node (ref "U3") (pin "3") (pinfunction "OUT2_2_3") (pintype "output"))
      (node (ref "U3") (pin "8") (pinfunction "OUT2_8") (pintype "output"))
    )
    (net (code "24") (name "MOTOR_L_PWM") (class "Default")
      (node (ref "U3") (pin "13") (pinfunction "IN1_13") (pintype "input"))
      (node (ref "U5") (pin "15") (pinfunction "PA5_15") (pintype "bidirectional"))
    )
    (net (code "25") (name "MOTOR_R_DIR") (class "Default")
      (node (ref "U2") (pin "5") (pinfunction "IN2_5") (pintype "input"))
      (node (ref "U5") (pin "19") (pinfunction "PB1_19") (pintype "bidirectional"))
    )
    (net (code "26") (name "MOTOR_R_OUT1") (class "Default")
      (node (ref "TP3") (pin "TP") (pinfunction "TP_TP") (pintype "input"))
      (node (ref "U2") (pin "1") (pinfunction "OUT1_2_1") (pintype "output"))
      (node (ref "U2") (pin "10") (pinfunction "OUT1_10") (pintype "output"))
    )
    (net (code "27") (name "MOTOR_R_OUT2") (class "Default")
      (node (ref "TP4") (pin "TP") (pinfunction "TP_TP") (pintype "input"))
      (node (ref "U2") (pin "3") (pinfunction "OUT2_2_3") (pintype "output"))
      (node (ref "U2") (pin "8") (pinfunction "OUT2_8") (pintype "output"))
    )
    (net (code "28") (name "MOTOR_R_PWM") (class "Default")
      (node (ref "U2") (pin "13") (pinfunction "IN1_13") (pintype "input"))
      (node (ref "U5") (pin "21") (pinfunction "PB10_21") (pintype "bidirectional"))
    )
    (net (code "29") (name "MOTOR_STBY") (class "Default")
      (node (ref "U2") (pin "14") (pinfunction "EN1_14") (pintype "input"))
      (node (ref "U2") (pin "4") (pinfunction "EN2_4") (pintype "input"))
      (node (ref "U3") (pin "14") (pinfunction "EN1_14") (pintype "input"))
      (node (ref "U3") (pin "4") (pinfunction "EN2_4") (pintype "input"))
      (node (ref "U5") (pin "20") (pinfunction "PB2_20") (pintype "bidirectional"))
    )
    (net (code "30") (name "NRST") (class "Default")
      (node (ref "C21") (pin "1") (pinfunction "1_1") (pintype "passive"))
      (node (ref "K1") (pin "5") (pinfunction "5_5") (pintype "passive"))
      (node (ref "RESET") (pin "1") (pinfunction "1_1") (pintype "passive"))
      (node (ref "RESET") (pin "2") (pinfunction "2_2") (pintype "passive"))
      (node (ref "U5") (pin "7") (pinfunction "NRST_7") (pintype "bidirectional"))
    )
    (net (code "31") (name "Net-(D3-A)") (class "Default")
      (node (ref "D3") (pin "1") (pinfunction "A_1") (pintype "passive"))
      (node (ref "SPK1") (pin "-") (pinfunction "+_-") (pintype "passive"))
      (node (ref "UBUZ") (pin "3") (pinfunction "D_3") (pintype "passive"))
    )
    (net (code "32") (name "Net-(IR_LED_FL-C)") (class "Default")
      (node (ref "IR_LED_FL") (pin "K") (pinfunction "C_K") (pintype "passive"))
      (node (ref "UFL") (pin "3") (pinfunction "D_3") (pintype "passive"))
    )
    (net (code "33") (name "Net-(IR_LED_FL-PadA)") (class "Default")
      (node (ref "IR_LED_FL") (pin "A") (pinfunction "A_A") (pintype "passive"))
      (node (ref "R1FL") (pin "1") (pinfunction "1_1") (pintype "passive"))
    )
    (net (code "34") (name "Net-(IR_LED_FR-C)") (class "Default")
      (node (ref "IR_LED_FR") (pin "K") (pinfunction "C_K") (pintype "passive"))
      (node (ref "UFR") (pin "3") (pinfunction "D_3") (pintype "passive"))
    )
    (net (code "35") (name "Net-(IR_LED_FR-PadA)") (class "Default")
      (node (ref "IR_LED_FR") (pin "A") (pinfunction "A_A") (pintype "passive"))
      (node (ref "R1FR") (pin "1") (pinfunction "1_1") (pintype "passive"))
    )
    (net (code "36") (name "Net-(IR_LED_L-C)") (class "Default")
      (node (ref "IR_LED_L") (pin "K") (pinfunction "C_K") (pintype "passive"))
      (node (ref "UL") (pin "3") (pinfunction "D_3") (pintype "passive"))
    )
    (net (code "37") (name "Net-(IR_LED_L-PadA)") (class "Default")
      (node (ref "IR_LED_L") (pin "A") (pinfunction "A_A") (pintype "passive"))
      (node (ref "R1L") (pin "1") (pinfunction "1_1") (pintype "passive"))
    )
    (net (code "38") (name "Net-(IR_LED_R-C)") (class "Default")
      (node (ref "IR_LED_R") (pin "K") (pinfunction "C_K") (pintype "passive"))
      (node (ref "UR") (pin "3") (pinfunction "D_3") (pintype "passive"))
    )
    (net (code "39") (name "Net-(IR_LED_R-PadA)") (class "Default")
      (node (ref "IR_LED_R") (pin "A") (pinfunction "A_A") (pintype "passive"))
      (node (ref "R1R") (pin "1") (pinfunction "1_1") (pintype "passive"))
    )
    (net (code "40") (name "Net-(LED1-PadA)") (class "Default")
      (node (ref "LED1") (pin "A") (pinfunction "A_A") (pintype "passive"))
      (node (ref "R26") (pin "1") (pinfunction "1_1") (pintype "passive"))
    )
    (net (code "41") (name "Net-(LED2-PadA)") (class "Default")
      (node (ref "LED2") (pin "A") (pinfunction "A_A") (pintype "passive"))
      (node (ref "R27") (pin "1") (pinfunction "1_1") (pintype "passive"))
    )
    (net (code "42") (name "Net-(LED3-PadA)") (class "Default")
      (node (ref "LED3") (pin "A") (pinfunction "A_A") (pintype "passive"))
      (node (ref "R28") (pin "1") (pinfunction "1_1") (pintype "passive"))
    )
    (net (code "43") (name "Net-(P-LED-PadA)") (class "Default")
      (node (ref "P-LED") (pin "A") (pinfunction "A_A") (pintype "passive"))
      (node (ref "R25") (pin "1") (pinfunction "1_1") (pintype "passive"))
    )
    (net (code "44") (name "Net-(Q2-G)") (class "Default")
      (node (ref "POWER") (pin "2") (pinfunction "2_2") (pintype "passive"))
      (node (ref "Q2") (pin "1") (pinfunction "G_1") (pintype "passive"))
      (node (ref "R12") (pin "1") (pinfunction "1_1") (pintype "passive"))
    )
    (net (code "45") (name "Net-(Q2-S)") (class "Default")
      (node (ref "P1") (pin "2") (pinfunction "2_2") (pintype "passive"))
      (node (ref "Q2") (pin "2") (pinfunction "S_2") (pintype "passive"))
      (node (ref "R12") (pin "2") (pinfunction "2_2") (pintype "passive"))
    )
    (net (code "46") (name "Net-(U5B-VCAP_1)") (class "Default")
      (node (ref "C_MCU-C") (pin "1") (pinfunction "1_1") (pintype "passive"))
      (node (ref "U5") (pin "22") (pinfunction "VCAP_1_22") (pintype "power_in"))
    )
    (net (code "47") (name "Net-(U6-~{WP})") (class "Default")
      (node (ref "R1") (pin "2") (pinfunction "2_2") (pintype "passive"))
      (node (ref "U6") (pin "3") (pinfunction "~{WP}_3") (pintype "input"))
    )
    (net (code "48") (name "PUSH_IN_1") (class "Default")
      (node (ref "MODE") (pin "1") (pinfunction "1_1") (pintype "passive"))
      (node (ref "MODE") (pin "2") (pinfunction "2_2") (pintype "passive"))
      (node (ref "R3") (pin "1") (pinfunction "1_1") (pintype "passive"))
      (node (ref "U5") (pin "5") (pinfunction "PH0-OSC_IN_5") (pintype "bidirectional"))
    )
    (net (code "49") (name "SENSOR_FL") (class "Default")
      (node (ref "PT_FL") (pin "K") (pinfunction "C_K") (pintype "passive"))
      (node (ref "R2FL") (pin "2") (pinfunction "2_2") (pintype "passive"))
      (node (ref "U5") (pin "12") (pinfunction "PA2_12") (pintype "bidirectional"))
    )
    (net (code "50") (name "SENSOR_FR") (class "Default")
      (node (ref "PT_FR") (pin "K") (pinfunction "C_K") (pintype "passive"))
      (node (ref "R2FR") (pin "2") (pinfunction "2_2") (pintype "passive"))
      (node (ref "U5") (pin "10") (pinfunction "PA0_10") (pintype "bidirectional"))
    )
    (net (code "51") (name "SENSOR_L") (class "Default")
      (node (ref "PT_L") (pin "K") (pinfunction "C_K") (pintype "passive"))
      (node (ref "R2L") (pin "2") (pinfunction "2_2") (pintype "passive"))
      (node (ref "U5") (pin "13") (pinfunction "PA3_13") (pintype "bidirectional"))
    )
    (net (code "52") (name "SENSOR_R") (class "Default")
      (node (ref "PT_R") (pin "K") (pinfunction "C_K") (pintype "passive"))
      (node (ref "R2R") (pin "2") (pinfunction "2_2") (pintype "passive"))
      (node (ref "U5") (pin "11") (pinfunction "PA1_11") (pintype "bidirectional"))
    )
    (net (code "53") (name "SPI2_MISO") (class "Default")
      (node (ref "U4") (pin "1") (pinfunction "SDO/SA0_1") (pintype "bidirectional"))
      (node (ref "U5") (pin "27") (pinfunction "PB14_27") (pintype "bidirectional"))
      (node (ref "U6") (pin "2") (pinfunction "SO_2") (pintype "output"))
    )
    (net (code "54") (name "SPI2_MOSI") (class "Default")
      (node (ref "U4") (pin "14") (pinfunction "SDA_14") (pintype "bidirectional"))
      (node (ref "U5") (pin "28") (pinfunction "PB15_28") (pintype "bidirectional"))
      (node (ref "U6") (pin "5") (pinfunction "SI_5") (pintype "input"))
    )
    (net (code "55") (name "SPI2_SCK") (class "Default")
      (node (ref "U4") (pin "13") (pinfunction "SCL_13") (pintype "input"))
      (node (ref "U5") (pin "26") (pinfunction "PB13_26") (pintype "bidirectional"))
      (node (ref "U6") (pin "6") (pinfunction "SCK_6") (pintype "input"))
    )
    (net (code "56") (name "SWCLK") (class "Default")
      (node (ref "K1") (pin "4") (pinfunction "4_4") (pintype "passive"))
      (node (ref "U5") (pin "37") (pinfunction "PA14_37") (pintype "bidirectional"))
    )
    (net (code "57") (name "SWDIO") (class "Default")
      (node (ref "K1") (pin "3") (pinfunction "3_3") (pintype "passive"))
      (node (ref "U5") (pin "34") (pinfunction "PA13_34") (pintype "bidirectional"))
    )
    (net (code "58") (name "SWO") (class "Default")
      (node (ref "K1") (pin "10") (pinfunction "10_10") (pintype "passive"))
      (node (ref "U5") (pin "39") (pinfunction "PB3_39") (pintype "bidirectional"))
    )
    (net (code "59") (name "USART1_RX") (class "Default")
      (node (ref "K1") (pin "9") (pinfunction "9_9") (pintype "passive"))
      (node (ref "U5") (pin "31") (pinfunction "PA10_31") (pintype "bidirectional"))
    )
    (net (code "60") (name "USART1_TX") (class "Default")
      (node (ref "K1") (pin "8") (pinfunction "8_8") (pintype "passive"))
      (node (ref "U5") (pin "30") (pinfunction "PA9_30") (pintype "bidirectional"))
    )
    (net (code "61") (name "VOL_CHECK") (class "Default")
      (node (ref "R4") (pin "1") (pinfunction "1_1") (pintype "passive"))
      (node (ref "R5") (pin "2") (pinfunction "2_2") (pintype "passive"))
      (node (ref "U5") (pin "18") (pinfunction "PB0_18") (pintype "bidirectional"))
    )
    (net (code "62") (name "unconnected-(POWER-Pad3)") (class "Default")
      (node (ref "POWER") (pin "3") (pinfunction "3_3") (pintype "passive"))
    )
    (net (code "63") (name "unconnected-(U2-CM1-Pad11)") (class "Default")
      (node (ref "U2") (pin "11") (pinfunction "CM1_11") (pintype "output"))
    )
    (net (code "64") (name "unconnected-(U2-CM2-Pad7)") (class "Default")
      (node (ref "U2") (pin "7") (pinfunction "CM2_7") (pintype "output"))
    )
    (net (code "65") (name "unconnected-(U2-NFAULT-Pad12)") (class "Default")
      (node (ref "U2") (pin "12") (pinfunction "NFAULT_12") (pintype "output"))
    )
    (net (code "66") (name "unconnected-(U3-CM1-Pad11)") (class "Default")
      (node (ref "U3") (pin "11") (pinfunction "CM1_11") (pintype "output"))
    )
    (net (code "67") (name "unconnected-(U3-CM2-Pad7)") (class "Default")
      (node (ref "U3") (pin "7") (pinfunction "CM2_7") (pintype "output"))
    )
    (net (code "68") (name "unconnected-(U3-NFAULT-Pad12)") (class "Default")
      (node (ref "U3") (pin "12") (pinfunction "NFAULT_12") (pintype "output"))
    )
    (net (code "69") (name "unconnected-(U4-INT1-Pad4)") (class "Default")
      (node (ref "U4") (pin "4") (pinfunction "INT1_4") (pintype "output"))
    )
    (net (code "70") (name "unconnected-(U4-INT2-Pad9)") (class "Default")
      (node (ref "U4") (pin "9") (pinfunction "INT2_9") (pintype "output"))
    )
    (net (code "71") (name "unconnected-(U4-OCS_AUX-Pad10)") (class "Default")
      (node (ref "U4") (pin "10") (pinfunction "OCS_AUX_10") (pintype "bidirectional"))
    )
    (net (code "72") (name "unconnected-(U4-SDO_AUX-Pad11)") (class "Default")
      (node (ref "U4") (pin "11") (pinfunction "SDO_AUX_11") (pintype "bidirectional"))
    )
    (net (code "73") (name "unconnected-(U5A-PA12-Pad33)") (class "Default")
      (node (ref "U5") (pin "33") (pinfunction "PA12_33") (pintype "bidirectional"))
    )
    (net (code "74") (name "unconnected-(U5A-PB4-Pad40)") (class "Default")
      (node (ref "U5") (pin "40") (pinfunction "PB4_40") (pintype "bidirectional"))
    )
    (net (code "75") (name "unconnected-(U6-DNU-Pad7)") (class "Default")
      (node (ref "U6") (pin "7") (pinfunction "DNU_7") (pintype "passive"))
    )
  )
)
